# 2_0_LCD.net
KiCad netlist of a schematic drawn in Altium Designer
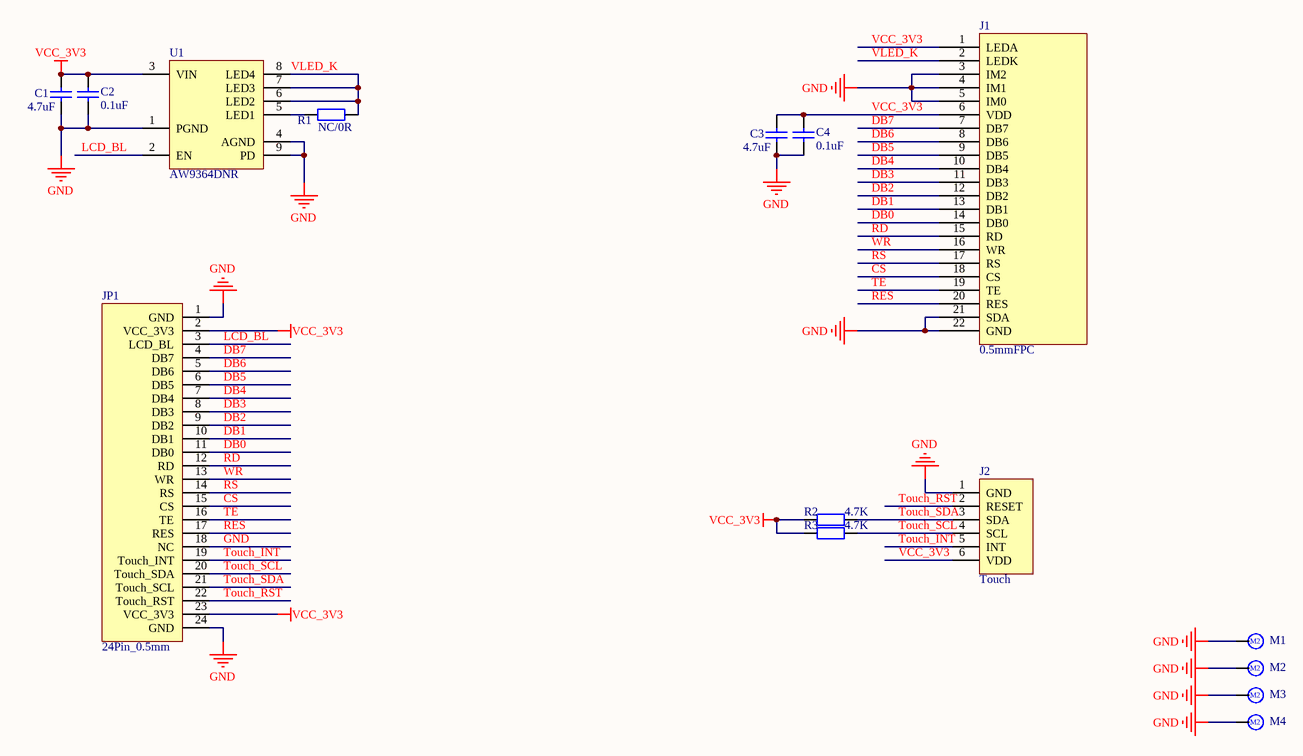
[diagram p0: 2.0_LCD.SchDoc]

(export (version "E")
  (design (tool "Eeschema 10.0.6"))
  (components
    (comp (ref "C1")
      (value "4.7uF")
      (footprint "C0603_L")
      (description "贴片电容")
      (libsource (lib "0.1 - 电阻-电容-电感-晶振-晶体-磁珠-电位器") (part "C"))
    )
    (comp (ref "C2")
      (value "0.1uF")
      (footprint "C0402_L")
      (description "贴片电容")
      (libsource (lib "0.1 - 电阻-电容-电感-晶振-晶体-磁珠-电位器") (part "C"))
    )
    (comp (ref "C3")
      (value "4.7uF")
      (footprint "C0603_L")
      (description "贴片电容")
      (libsource (lib "0.1 - 电阻-电容-电感-晶振-晶体-磁珠-电位器") (part "C"))
    )
    (comp (ref "C4")
      (value "0.1uF")
      (footprint "C0402_L")
      (description "贴片电容")
      (libsource (lib "0.1 - 电阻-电容-电感-晶振-晶体-磁珠-电位器") (part "C"))
    )
    (comp (ref "J1")
      (value "0.5mmFPC")
      (footprint "FPC0.5-WT-22P")
      (libsource (lib "USER_Lib") (part "中景园2.0寸屏幕FPC接口"))
    )
    (comp (ref "J2")
      (value "Touch")
      (footprint "FPC0.5-WT-6P")
      (libsource (lib "USER_Lib") (part "深圳市大显伟业2.0寸触摸屏"))
    )
    (comp (ref "JP1")
      (value "24Pin_0.5mm")
      (footprint "FPC0.5-WT-24P")
      (description "屏幕板外接座")
      (libsource (lib "USER_Lib") (part "屏幕板FPC"))
    )
    (comp (ref "M1")
      (value "M2")
      (footprint "M2*4.5*2.5*0.8*3.3")
      (description "M2孔支撑柱")
      (libsource (lib "USER_Lib") (part "M2系列"))
    )
    (comp (ref "M2")
      (value "M2")
      (footprint "M2*4.5*2.5*0.8*3.3")
      (description "M2孔支撑柱")
      (libsource (lib "USER_Lib") (part "M2系列"))
    )
    (comp (ref "M3")
      (value "M2")
      (footprint "M2*4.5*2.5*0.8*3.3")
      (description "M2孔支撑柱")
      (libsource (lib "USER_Lib") (part "M2系列"))
    )
    (comp (ref "M4")
      (value "M2")
      (footprint "M2*4.5*2.5*0.8*3.3")
      (description "M2孔支撑柱")
      (libsource (lib "USER_Lib") (part "M2系列"))
    )
    (comp (ref "R1")
      (value "NC/0R")
      (footprint "R0402_L")
      (description "贴片电阻")
      (libsource (lib "0.1 - 电阻-电容-电感-晶振-晶体-磁珠-电位器") (part "R"))
    )
    (comp (ref "R2")
      (value "4.7K")
      (footprint "R0402_L")
      (description "贴片电阻")
      (libsource (lib "0.1 - 电阻-电容-电感-晶振-晶体-磁珠-电位器") (part "R"))
    )
    (comp (ref "R3")
      (value "4.7K")
      (footprint "R0402_L")
      (description "贴片电阻")
      (libsource (lib "0.1 - 电阻-电容-电感-晶振-晶体-磁珠-电位器") (part "R"))
    )
    (comp (ref "U1")
      (value "AW9364DNR")
      (footprint "DFN2X2-8L")
      (description "并联调光背光驱动")
      (libsource (lib "USER_Lib") (part "AW9364DNR"))
    )
  )
  (nets
    (net (code "1") (name "/CS") (class "Default")
      (node (ref "J1") (pin "18") (pinfunction "CS_18") (pintype "passive"))
      (node (ref "JP1") (pin "15") (pinfunction "CS_15") (pintype "passive"))
    )
    (net (code "2") (name "/DB0") (class "Default")
      (node (ref "J1") (pin "14") (pinfunction "DB0_14") (pintype "passive"))
      (node (ref "JP1") (pin "11") (pinfunction "DB0_11") (pintype "passive"))
    )
    (net (code "3") (name "/DB1") (class "Default")
      (node (ref "J1") (pin "13") (pinfunction "DB1_13") (pintype "passive"))
      (node (ref "JP1") (pin "10") (pinfunction "DB1_10") (pintype "passive"))
    )
    (net (code "4") (name "/DB2") (class "Default")
      (node (ref "J1") (pin "12") (pinfunction "DB2_12") (pintype "passive"))
      (node (ref "JP1") (pin "9") (pinfunction "DB2_9") (pintype "passive"))
    )
    (net (code "5") (name "/DB3") (class "Default")
      (node (ref "J1") (pin "11") (pinfunction "DB3_11") (pintype "passive"))
      (node (ref "JP1") (pin "8") (pinfunction "DB3_8") (pintype "passive"))
    )
    (net (code "6") (name "/DB4") (class "Default")
      (node (ref "J1") (pin "10") (pinfunction "DB4_10") (pintype "passive"))
      (node (ref "JP1") (pin "7") (pinfunction "DB4_7") (pintype "passive"))
    )
    (net (code "7") (name "/DB5") (class "Default")
      (node (ref "J1") (pin "9") (pinfunction "DB5_9") (pintype "passive"))
      (node (ref "JP1") (pin "6") (pinfunction "DB5_6") (pintype "passive"))
    )
    (net (code "8") (name "/DB6") (class "Default")
      (node (ref "J1") (pin "8") (pinfunction "DB6_8") (pintype "passive"))
      (node (ref "JP1") (pin "5") (pinfunction "DB6_5") (pintype "passive"))
    )
    (net (code "9") (name "/DB7") (class "Default")
      (node (ref "J1") (pin "7") (pinfunction "DB7_7") (pintype "passive"))
      (node (ref "JP1") (pin "4") (pinfunction "DB7_4") (pintype "passive"))
    )
    (net (code "10") (name "/LCD_BL") (class "Default")
      (node (ref "JP1") (pin "3") (pinfunction "LCD_BL_3") (pintype "passive"))
      (node (ref "U1") (pin "2") (pinfunction "EN_2") (pintype "passive"))
    )
    (net (code "11") (name "/RD") (class "Default")
      (node (ref "J1") (pin "15") (pinfunction "RD_15") (pintype "passive"))
      (node (ref "JP1") (pin "12") (pinfunction "RD_12") (pintype "passive"))
    )
    (net (code "12") (name "/RES") (class "Default")
      (node (ref "J1") (pin "20") (pinfunction "RES_20") (pintype "passive"))
      (node (ref "JP1") (pin "17") (pinfunction "RES_17") (pintype "passive"))
    )
    (net (code "13") (name "/RS") (class "Default")
      (node (ref "J1") (pin "17") (pinfunction "RS_17") (pintype "passive"))
      (node (ref "JP1") (pin "14") (pinfunction "RS_14") (pintype "passive"))
    )
    (net (code "14") (name "/TE") (class "Default")
      (node (ref "J1") (pin "19") (pinfunction "TE_19") (pintype "passive"))
      (node (ref "JP1") (pin "16") (pinfunction "TE_16") (pintype "passive"))
    )
    (net (code "15") (name "/Touch_INT") (class "Default")
      (node (ref "J2") (pin "5") (pinfunction "INT_5") (pintype "passive"))
      (node (ref "JP1") (pin "19") (pinfunction "Touch_INT_19") (pintype "passive"))
    )
    (net (code "16") (name "/Touch_RST") (class "Default")
      (node (ref "J2") (pin "2") (pinfunction "RESET_2") (pintype "passive"))
      (node (ref "JP1") (pin "22") (pinfunction "Touch_RST_22") (pintype "passive"))
    )
    (net (code "17") (name "/Touch_SCL") (class "Default")
      (node (ref "J2") (pin "4") (pinfunction "SCL_4") (pintype "passive"))
      (node (ref "JP1") (pin "20") (pinfunction "Touch_SDA_20") (pintype "passive"))
      (node (ref "R3") (pin "2") (pinfunction "2_2") (pintype "passive"))
    )
    (net (code "18") (name "/Touch_SDA") (class "Default")
      (node (ref "J2") (pin "3") (pinfunction "SDA_3") (pintype "passive"))
      (node (ref "JP1") (pin "21") (pinfunction "Touch_SCL_21") (pintype "passive"))
      (node (ref "R2") (pin "2") (pinfunction "2_2") (pintype "passive"))
    )
    (net (code "19") (name "/VLED_K") (class "Default")
      (node (ref "J1") (pin "2") (pinfunction "LEDK_2") (pintype "passive"))
      (node (ref "R1") (pin "1") (pinfunction "1_1") (pintype "passive"))
      (node (ref "U1") (pin "6") (pinfunction "LED2_6") (pintype "passive"))
      (node (ref "U1") (pin "7") (pinfunction "LED3_7") (pintype "passive"))
      (node (ref "U1") (pin "8") (pinfunction "LED4_8") (pintype "passive"))
    )
    (net (code "20") (name "/WR") (class "Default")
      (node (ref "J1") (pin "16") (pinfunction "WR_16") (pintype "passive"))
      (node (ref "JP1") (pin "13") (pinfunction "WR_13") (pintype "passive"))
    )
    (net (code "21") (name "GND") (class "Default")
      (node (ref "C1") (pin "1") (pinfunction "1_1") (pintype "passive"))
      (node (ref "C2") (pin "1") (pinfunction "1_1") (pintype "passive"))
      (node (ref "C3") (pin "1") (pinfunction "1_1") (pintype "passive"))
      (node (ref "C4") (pin "1") (pinfunction "1_1") (pintype "passive"))
      (node (ref "J1") (pin "21") (pinfunction "SDA_21") (pintype "passive"))
      (node (ref "J1") (pin "22") (pinfunction "GND_22") (pintype "passive"))
      (node (ref "J1") (pin "3") (pinfunction "IM2_3") (pintype "passive"))
      (node (ref "J1") (pin "4") (pinfunction "IM1_4") (pintype "passive"))
      (node (ref "J1") (pin "5") (pinfunction "IM0_5") (pintype "passive"))
      (node (ref "J2") (pin "1") (pinfunction "GND_1") (pintype "passive"))
      (node (ref "JP1") (pin "1") (pinfunction "GND_1") (pintype "passive"))
      (node (ref "JP1") (pin "18") (pinfunction "NC_18") (pintype "passive"))
      (node (ref "JP1") (pin "24") (pinfunction "GND_24") (pintype "passive"))
      (node (ref "M1") (pin "1") (pinfunction "1_1") (pintype "passive"))
      (node (ref "M2") (pin "1") (pinfunction "1_1") (pintype "passive"))
      (node (ref "M3") (pin "1") (pinfunction "1_1") (pintype "passive"))
      (node (ref "M4") (pin "1") (pinfunction "1_1") (pintype "passive"))
      (node (ref "U1") (pin "1") (pinfunction "PGND_1") (pintype "passive"))
      (node (ref "U1") (pin "4") (pinfunction "AGND_4") (pintype "passive"))
      (node (ref "U1") (pin "9") (pinfunction "PD_9") (pintype "passive"))
    )
    (net (code "22") (name "Net-(U1-LED1)") (class "Default")
      (node (ref "R1") (pin "2") (pinfunction "2_2") (pintype "passive"))
      (node (ref "U1") (pin "5") (pinfunction "LED1_5") (pintype "passive"))
    )
    (net (code "23") (name "VCC_3V3") (class "Default")
      (node (ref "C1") (pin "2") (pinfunction "2_2") (pintype "passive"))
      (node (ref "C2") (pin "2") (pinfunction "2_2") (pintype "passive"))
      (node (ref "C3") (pin "2") (pinfunction "2_2") (pintype "passive"))
      (node (ref "C4") (pin "2") (pinfunction "2_2") (pintype "passive"))
      (node (ref "J1") (pin "1") (pinfunction "LEDA_1") (pintype "passive"))
      (node (ref "J1") (pin "6") (pinfunction "VDD_6") (pintype "passive"))
      (node (ref "J2") (pin "6") (pinfunction "VDD_6") (pintype "passive"))
      (node (ref "JP1") (pin "2") (pinfunction "VCC_3V3_2") (pintype "passive"))
      (node (ref "JP1") (pin "23") (pinfunction "VCC_3V3_23") (pintype "passive"))
      (node (ref "R2") (pin "1") (pinfunction "1_1") (pintype "passive"))
      (node (ref "R3") (pin "1") (pinfunction "1_1") (pintype "passive"))
      (node (ref "U1") (pin "3") (pinfunction "VIN_3") (pintype "passive"))
    )
  )
)
